# Mono_Bass_TPA3138D2.net
KiCad netlist of a schematic drawn in Altium Designer
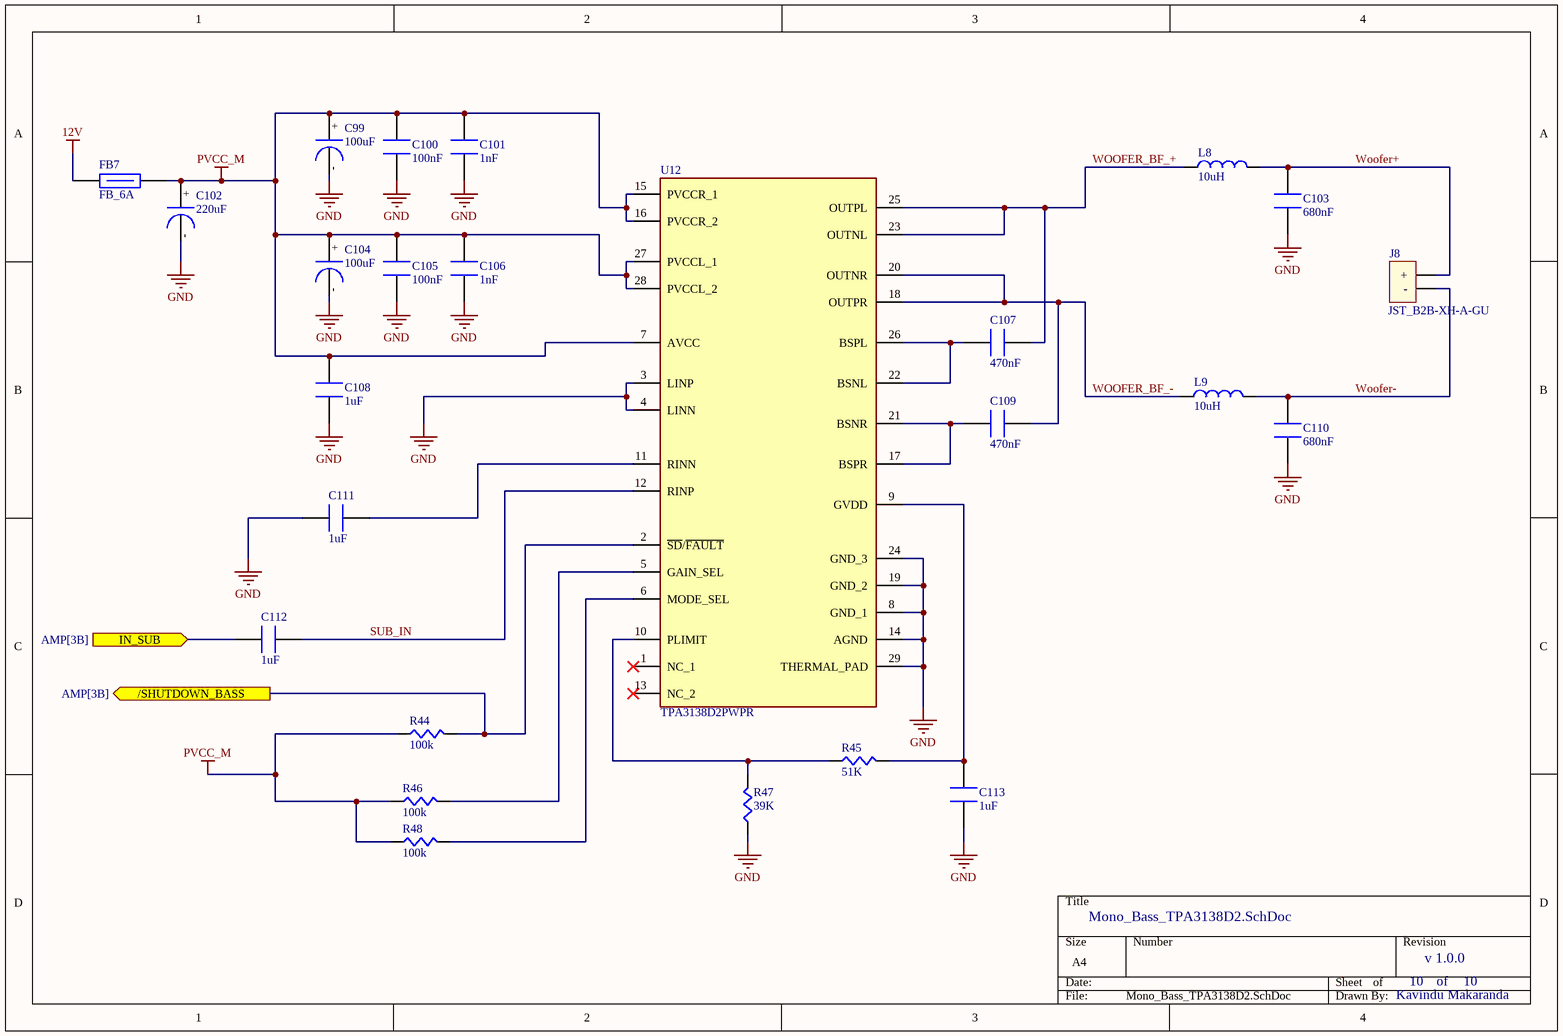
[diagram p0: Mono_Bass_TPA3138D2.SchDoc]

(export (version "E")
  (design (tool "Eeschema 10.0.6"))
  (components
    (comp (ref "C99")
      (value "100uF")
      (footprint "CAPD6.3XL6.3X77M")
      (libsource (lib "Schlib1") (part "CPD6.3XL7.7_100uF_POLY"))
    )
    (comp (ref "C100")
      (value "100nF")
      (footprint "CAPC0603X8N")
      (libsource (lib "Schlib1") (part "CC0603_100nF_X7R"))
    )
    (comp (ref "C101")
      (value "1nF")
      (footprint "CAPC0603X8N")
      (libsource (lib "Schlib1") (part "CC0603_1nF_X7R"))
    )
    (comp (ref "C102")
      (value "220uF")
      (footprint "CAPD6.3XL6.3X77M")
      (libsource (lib "Schlib1") (part "CPD6.3XL7.7_220uF_POLY"))
    )
    (comp (ref "C103")
      (value "680nF")
      (footprint "CAPC1206X18N")
      (libsource (lib "Schlib1") (part "CC1206_680nF_X7R"))
    )
    (comp (ref "C104")
      (value "100uF")
      (footprint "CAPD6.3XL6.3X77M")
      (libsource (lib "Schlib1") (part "CPD6.3XL7.7_100uF_POLY"))
    )
    (comp (ref "C105")
      (value "100nF")
      (footprint "CAPC0603X8N")
      (libsource (lib "Schlib1") (part "CC0603_100nF_X7R"))
    )
    (comp (ref "C106")
      (value "1nF")
      (footprint "CAPC0603X8N")
      (libsource (lib "Schlib1") (part "CC0603_1nF_X7R"))
    )
    (comp (ref "C107")
      (value "470nF")
      (footprint "CAPC1206X18N")
      (libsource (lib "Schlib1") (part "CC1206_470nF_X7R"))
    )
    (comp (ref "C108")
      (value "1uF")
      (footprint "CAP0805X13N")
      (description "C28323, CL21B105KBFNNNE, 1uF 50V X7R ±10% 0805 Multilayer Ceramic Capacitors MLCC - SMD/SMT ROHS")
      (libsource (lib "Schlib1") (part "CC0805_1uF_X7R"))
    )
    (comp (ref "C109")
      (value "470nF")
      (footprint "CAPC1206X18N")
      (libsource (lib "Schlib1") (part "CC1206_470nF_X7R"))
    )
    (comp (ref "C110")
      (value "680nF")
      (footprint "CAPC1206X18N")
      (libsource (lib "Schlib1") (part "CC1206_680nF_X7R"))
    )
    (comp (ref "C111")
      (value "1uF")
      (footprint "CAP0805X13N")
      (description "C28323, CL21B105KBFNNNE, 1uF 50V X7R ±10% 0805 Multilayer Ceramic Capacitors MLCC - SMD/SMT ROHS")
      (libsource (lib "Schlib1") (part "CC0805_1uF_X7R"))
    )
    (comp (ref "C112")
      (value "1uF")
      (footprint "CAP0805X13N")
      (description "C28323, CL21B105KBFNNNE, 1uF 50V X7R ±10% 0805 Multilayer Ceramic Capacitors MLCC - SMD/SMT ROHS")
      (libsource (lib "Schlib1") (part "CC0805_1uF_X7R"))
    )
    (comp (ref "C113")
      (value "1uF")
      (footprint "CAP0805X13N")
      (description "C28323, CL21B105KBFNNNE, 1uF 50V X7R ±10% 0805 Multilayer Ceramic Capacitors MLCC - SMD/SMT ROHS")
      (libsource (lib "Schlib1") (part "CC0805_1uF_X7R"))
    )
    (comp (ref "FB7")
      (value "FB_6A")
      (footprint "FB0805X12N")
      (description "C136227, MPZ2012S300AT000, -55℃~+125℃ 1 10mΩ 30Ω@100MHz 6A ±25% 0805 Ferrite Beads ROHS")
      (libsource (lib "Schlib1") (part "FB0805_6A"))
    )
    (comp (ref "J8")
      (value "JST_B2B-XH-A-GU")
      (footprint "JST_B2B_XH_A_GU")
      (libsource (lib "Schlib1") (part "JST_B2B-XH-A-GU"))
    )
    (comp (ref "L8")
      (value "10uH")
      (footprint "INDC6060X45N")
      (libsource (lib "Schlib1") (part "IN0606_10uH_2.7A"))
    )
    (comp (ref "L9")
      (value "10uH")
      (footprint "INDC6060X45N")
      (libsource (lib "Schlib1") (part "IN0606_10uH_2.7A"))
    )
    (comp (ref "R44")
      (value "100k")
      (footprint "RECS0603X45N")
      (libsource (lib "Schlib1") (part "RESC0603_100K_THIN"))
    )
    (comp (ref "R45")
      (value "51K")
      (footprint "RECS0603X45N")
      (libsource (lib "Schlib1") (part "RESC0603_51K_THICK"))
    )
    (comp (ref "R46")
      (value "100k")
      (footprint "RECS0603X45N")
      (libsource (lib "Schlib1") (part "RESC0603_100K_THIN"))
    )
    (comp (ref "R47")
      (value "39K")
      (footprint "RECS0603X45N")
      (libsource (lib "Schlib1") (part "RESC0603_39K_THICK"))
    )
    (comp (ref "R48")
      (value "100k")
      (footprint "RECS0603X45N")
      (libsource (lib "Schlib1") (part "RESC0603_100K_THIN"))
    )
    (comp (ref "U12")
      (value "TPA3138D2PWPR")
      (footprint "SOP65P640X120-29N")
      (fields (field (name "MOUSER PART NUMBER") "595-TPA3138D2PWPR"))
      (libsource (lib "Schlib1") (part "TPA3138D2PWPR"))
    )
  )
  (nets
    (net (code "1") (name "/IN_SUB") (class "Default")
      (node (ref "C112") (pin "1") (pinfunction "1_1") (pintype "passive"))
    )
    (net (code "2") (name "/SUB_IN") (class "Default")
      (node (ref "C112") (pin "2") (pinfunction "2_2") (pintype "passive"))
      (node (ref "U12") (pin "12") (pinfunction "RINP_12") (pintype "passive"))
    )
    (net (code "3") (name "/WOOFER_BF_+") (class "Default")
      (node (ref "C107") (pin "2") (pinfunction "2_2") (pintype "passive"))
      (node (ref "L8") (pin "1") (pinfunction "1_1") (pintype "passive"))
      (node (ref "U12") (pin "23") (pinfunction "OUTNL_23") (pintype "passive"))
      (node (ref "U12") (pin "25") (pinfunction "OUTPL_25") (pintype "passive"))
    )
    (net (code "4") (name "/WOOFER_BF_-") (class "Default")
      (node (ref "C109") (pin "2") (pinfunction "2_2") (pintype "passive"))
      (node (ref "L9") (pin "1") (pinfunction "1_1") (pintype "passive"))
      (node (ref "U12") (pin "18") (pinfunction "OUTPR_18") (pintype "passive"))
      (node (ref "U12") (pin "20") (pinfunction "OUTNR_20") (pintype "passive"))
    )
    (net (code "5") (name "/Woofer+") (class "Default")
      (node (ref "C103") (pin "2") (pinfunction "2_2") (pintype "passive"))
      (node (ref "J8") (pin "1") (pinfunction "+_1") (pintype "passive"))
      (node (ref "L8") (pin "2") (pinfunction "2_2") (pintype "passive"))
    )
    (net (code "6") (name "/Woofer-") (class "Default")
      (node (ref "C110") (pin "2") (pinfunction "2_2") (pintype "passive"))
      (node (ref "J8") (pin "2") (pinfunction "-_2") (pintype "passive"))
      (node (ref "L9") (pin "2") (pinfunction "2_2") (pintype "passive"))
    )
    (net (code "7") (name "/{slash}SHUTDOWN_BASS") (class "Default")
      (node (ref "R44") (pin "2") (pinfunction "2_2") (pintype "passive"))
      (node (ref "U12") (pin "2") (pinfunction "~{SD}/~{FAULT}_2") (pintype "passive"))
    )
    (net (code "8") (name "12V") (class "Default")
      (node (ref "FB7") (pin "1") (pinfunction "1_1") (pintype "passive"))
    )
    (net (code "9") (name "GND") (class "Default")
      (node (ref "C100") (pin "1") (pinfunction "1_1") (pintype "passive"))
      (node (ref "C101") (pin "1") (pinfunction "1_1") (pintype "passive"))
      (node (ref "C102") (pin "2") (pinfunction "2_2") (pintype "passive"))
      (node (ref "C103") (pin "1") (pinfunction "1_1") (pintype "passive"))
      (node (ref "C104") (pin "2") (pinfunction "2_2") (pintype "passive"))
      (node (ref "C105") (pin "1") (pinfunction "1_1") (pintype "passive"))
      (node (ref "C106") (pin "1") (pinfunction "1_1") (pintype "passive"))
      (node (ref "C108") (pin "1") (pinfunction "1_1") (pintype "passive"))
      (node (ref "C110") (pin "1") (pinfunction "1_1") (pintype "passive"))
      (node (ref "C111") (pin "1") (pinfunction "1_1") (pintype "passive"))
      (node (ref "C113") (pin "1") (pinfunction "1_1") (pintype "passive"))
      (node (ref "C99") (pin "2") (pinfunction "2_2") (pintype "passive"))
      (node (ref "R47") (pin "1") (pinfunction "1_1") (pintype "passive"))
      (node (ref "U12") (pin "14") (pinfunction "AGND_14") (pintype "passive"))
      (node (ref "U12") (pin "19") (pinfunction "GND_2_19") (pintype "passive"))
      (node (ref "U12") (pin "24") (pinfunction "GND_3_24") (pintype "passive"))
      (node (ref "U12") (pin "29") (pinfunction "THERMAL_PAD_29") (pintype "passive"))
      (node (ref "U12") (pin "3") (pinfunction "LINP_3") (pintype "passive"))
      (node (ref "U12") (pin "4") (pinfunction "LINN_4") (pintype "passive"))
      (node (ref "U12") (pin "8") (pinfunction "GND_1_8") (pintype "passive"))
    )
    (net (code "10") (name "Net-(U12-BSNL)") (class "Default")
      (node (ref "C107") (pin "1") (pinfunction "1_1") (pintype "passive"))
      (node (ref "U12") (pin "22") (pinfunction "BSNL_22") (pintype "passive"))
      (node (ref "U12") (pin "26") (pinfunction "BSPL_26") (pintype "passive"))
    )
    (net (code "11") (name "Net-(U12-BSNR)") (class "Default")
      (node (ref "C109") (pin "1") (pinfunction "1_1") (pintype "passive"))
      (node (ref "U12") (pin "17") (pinfunction "BSPR_17") (pintype "passive"))
      (node (ref "U12") (pin "21") (pinfunction "BSNR_21") (pintype "passive"))
    )
    (net (code "12") (name "Net-(U12-GAIN_SEL)") (class "Default")
      (node (ref "R46") (pin "2") (pinfunction "2_2") (pintype "passive"))
      (node (ref "U12") (pin "5") (pinfunction "GAIN_SEL_5") (pintype "passive"))
    )
    (net (code "13") (name "Net-(U12-GVDD)") (class "Default")
      (node (ref "C113") (pin "2") (pinfunction "2_2") (pintype "passive"))
      (node (ref "R45") (pin "2") (pinfunction "2_2") (pintype "passive"))
      (node (ref "U12") (pin "9") (pinfunction "GVDD_9") (pintype "passive"))
    )
    (net (code "14") (name "Net-(U12-MODE_SEL)") (class "Default")
      (node (ref "R48") (pin "2") (pinfunction "2_2") (pintype "passive"))
      (node (ref "U12") (pin "6") (pinfunction "MODE_SEL_6") (pintype "passive"))
    )
    (net (code "15") (name "Net-(U12-PLIMIT)") (class "Default")
      (node (ref "R45") (pin "1") (pinfunction "1_1") (pintype "passive"))
      (node (ref "R47") (pin "2") (pinfunction "2_2") (pintype "passive"))
      (node (ref "U12") (pin "10") (pinfunction "PLIMIT_10") (pintype "passive"))
    )
    (net (code "16") (name "Net-(U12-RINN)") (class "Default")
      (node (ref "C111") (pin "2") (pinfunction "2_2") (pintype "passive"))
      (node (ref "U12") (pin "11") (pinfunction "RINN_11") (pintype "passive"))
    )
    (net (code "17") (name "PVCC_M") (class "Default")
      (node (ref "C100") (pin "2") (pinfunction "2_2") (pintype "passive"))
      (node (ref "C101") (pin "2") (pinfunction "2_2") (pintype "passive"))
      (node (ref "C102") (pin "1") (pinfunction "1_1") (pintype "passive"))
      (node (ref "C104") (pin "1") (pinfunction "1_1") (pintype "passive"))
      (node (ref "C105") (pin "2") (pinfunction "2_2") (pintype "passive"))
      (node (ref "C106") (pin "2") (pinfunction "2_2") (pintype "passive"))
      (node (ref "C108") (pin "2") (pinfunction "2_2") (pintype "passive"))
      (node (ref "C99") (pin "1") (pinfunction "1_1") (pintype "passive"))
      (node (ref "FB7") (pin "2") (pinfunction "2_2") (pintype "passive"))
      (node (ref "R44") (pin "1") (pinfunction "1_1") (pintype "passive"))
      (node (ref "R46") (pin "1") (pinfunction "1_1") (pintype "passive"))
      (node (ref "R48") (pin "1") (pinfunction "1_1") (pintype "passive"))
      (node (ref "U12") (pin "15") (pinfunction "PVCCR_1_15") (pintype "passive"))
      (node (ref "U12") (pin "16") (pinfunction "PVCCR_2_16") (pintype "passive"))
      (node (ref "U12") (pin "27") (pinfunction "PVCCL_1_27") (pintype "passive"))
      (node (ref "U12") (pin "28") (pinfunction "PVCCL_2_28") (pintype "passive"))
      (node (ref "U12") (pin "7") (pinfunction "AVCC_7") (pintype "passive"))
    )
    (net (code "18") (name "unconnected-(U12-NC_1-Pad1)") (class "Default")
      (node (ref "U12") (pin "1") (pinfunction "NC_1_1") (pintype "passive+no_connect"))
    )
    (net (code "19") (name "unconnected-(U12-NC_2-Pad13)") (class "Default")
      (node (ref "U12") (pin "13") (pinfunction "NC_2_13") (pintype "passive+no_connect"))
    )
  )
)
